# hpmon_pi_baseboard.net
KiCad netlist of a schematic drawn in EAGLE
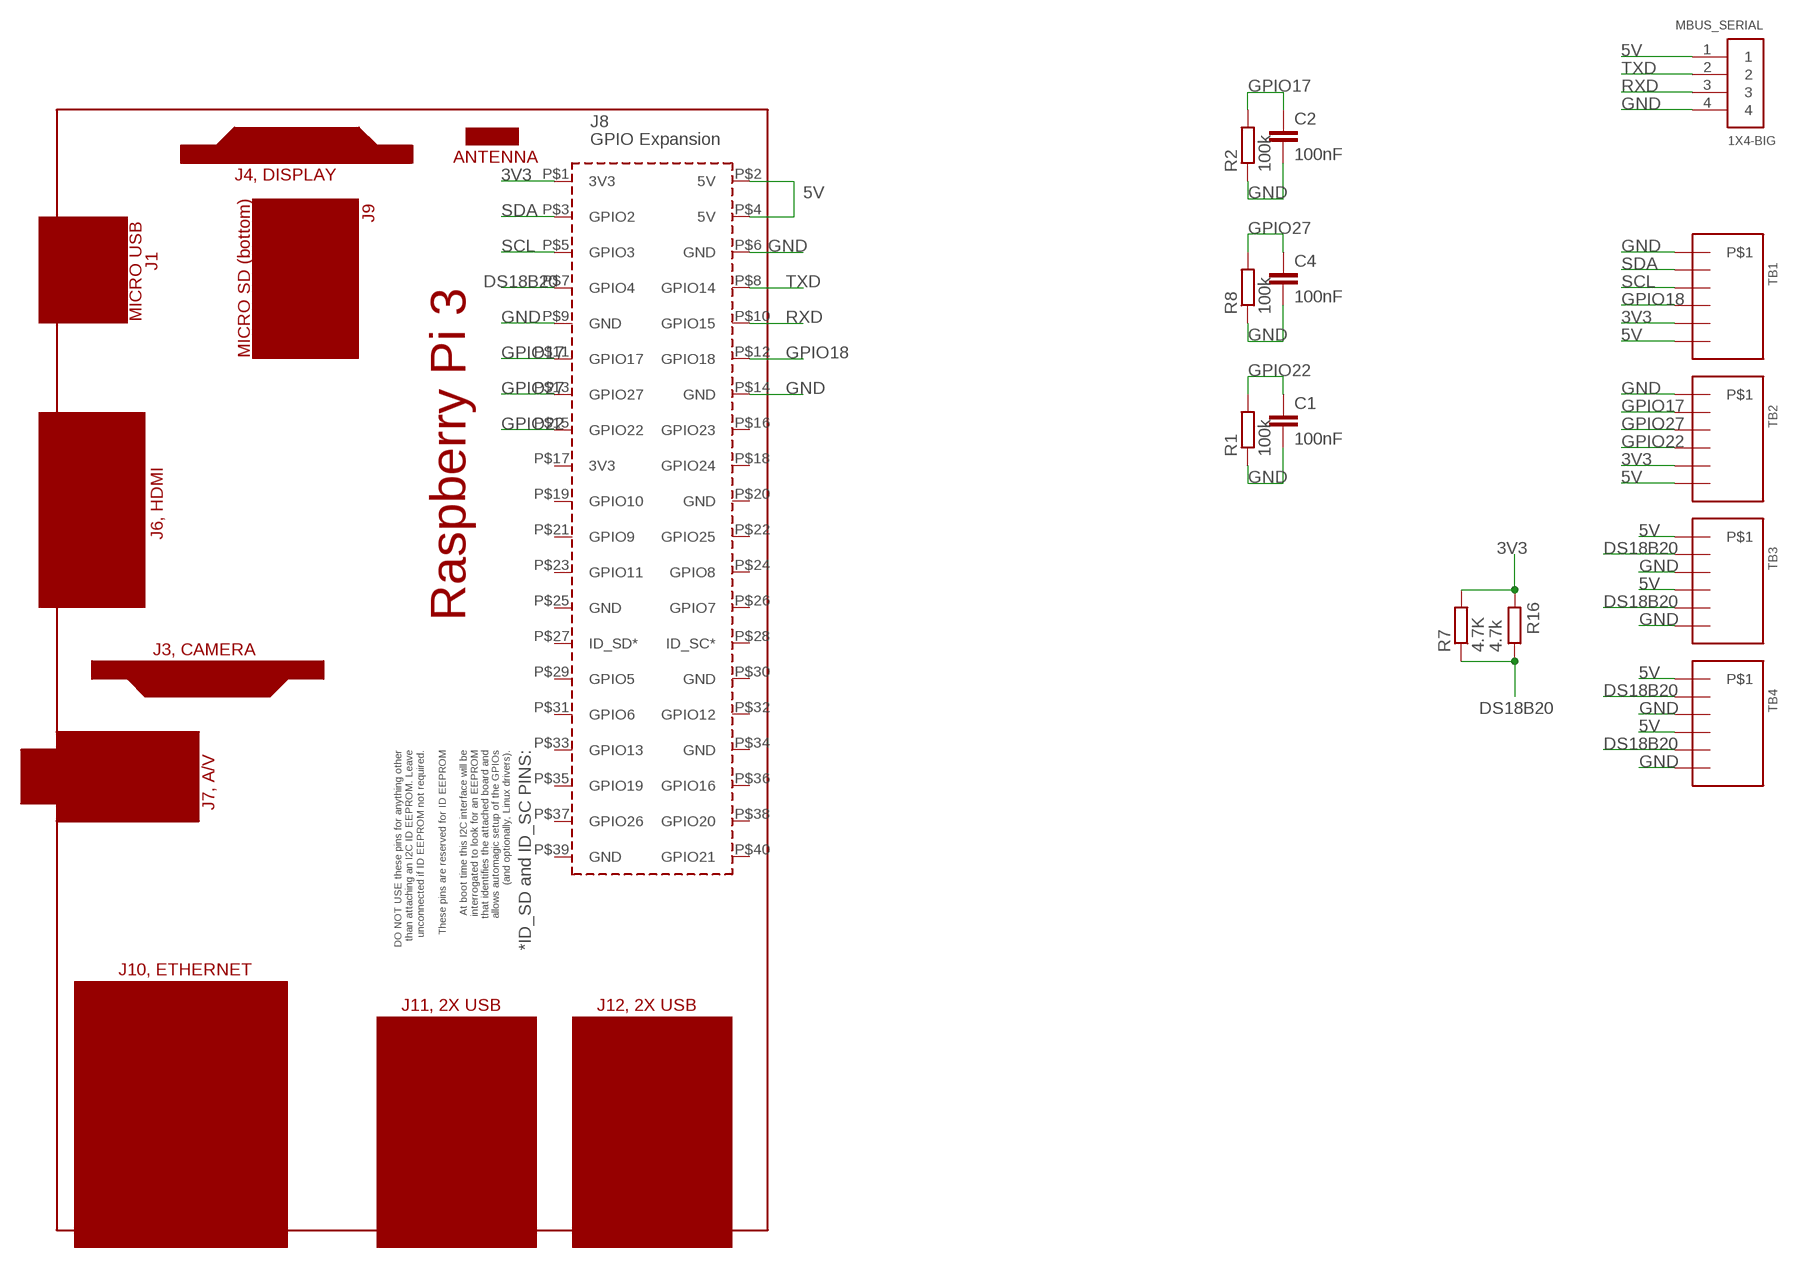
[diagram p0: schematic, sheet 1]

(export (version "E")
  (design (tool "Eeschema 10.0.6"))
  (components
    (comp (ref "C1")
      (value "100nF")
      (footprint "eagle-import:C025-024X044")
      (libsource (lib "eagle-import") (part "C-EU025-024X044"))
    )
    (comp (ref "C2")
      (value "100nF")
      (footprint "eagle-import:C025-024X044")
      (libsource (lib "eagle-import") (part "C-EU025-024X044"))
    )
    (comp (ref "C4")
      (value "100nF")
      (footprint "eagle-import:C025-024X044")
      (libsource (lib "eagle-import") (part "C-EU025-024X044"))
    )
    (comp (ref "MBUS_SERIAL")
      (value "1X4-BIG")
      (footprint "eagle-import:1X04-BIG")
      (libsource (lib "eagle-import") (part "1X4-BIG"))
    )
    (comp (ref "PCB1")
      (value "RPI3RPI3")
      (footprint "eagle-import:RPI3")
      (libsource (lib "eagle-import") (part "RPI3RPI3"))
    )
    (comp (ref "R1")
      (value "100k")
      (footprint "eagle-import:0207_2V")
      (libsource (lib "eagle-import") (part "R-EU_0207/2V"))
    )
    (comp (ref "R2")
      (value "100k")
      (footprint "eagle-import:0207_2V")
      (libsource (lib "eagle-import") (part "R-EU_0207/2V"))
    )
    (comp (ref "R7")
      (value "4.7K")
      (footprint "eagle-import:0204_7")
      (libsource (lib "eagle-import") (part "resistor_R-EU_0204/7"))
    )
    (comp (ref "R8")
      (value "100k")
      (footprint "eagle-import:0207_2V")
      (libsource (lib "eagle-import") (part "R-EU_0207/2V"))
    )
    (comp (ref "R16")
      (value "4.7k")
      (footprint "eagle-import:R0603")
      (libsource (lib "eagle-import") (part "R-EU_R0603"))
    )
    (comp (ref "TB1")
      (value "3.5MM_TB_X6")
      (footprint "eagle-import:3.5MM_X6")
      (libsource (lib "eagle-import") (part "3.5MM_TB_X6"))
    )
    (comp (ref "TB2")
      (value "3.5MM_TB_X6")
      (footprint "eagle-import:3.5MM_X6")
      (libsource (lib "eagle-import") (part "3.5MM_TB_X6"))
    )
    (comp (ref "TB3")
      (value "3.5MM_TB_X6")
      (footprint "eagle-import:3.5MM_X6")
      (libsource (lib "eagle-import") (part "3.5MM_TB_X6"))
    )
    (comp (ref "TB4")
      (value "3.5MM_TB_X6")
      (footprint "eagle-import:3.5MM_X6")
      (libsource (lib "eagle-import") (part "3.5MM_TB_X6"))
    )
  )
  (nets
    (net (code "1") (name "/3V3") (class "Default")
      (node (ref "PCB1") (pin "P$1") (pinfunction "3V3_P$1") (pintype "bidirectional"))
      (node (ref "R16") (pin "2") (pinfunction "2_2") (pintype "passive"))
      (node (ref "R7") (pin "2") (pinfunction "2_2") (pintype "passive"))
      (node (ref "TB1") (pin "P$5") (pinfunction "P$5_P$5") (pintype "bidirectional"))
      (node (ref "TB2") (pin "P$5") (pinfunction "P$5_P$5") (pintype "bidirectional"))
    )
    (net (code "2") (name "/5V") (class "Default")
      (node (ref "MBUS_SERIAL") (pin "1") (pinfunction "1_1") (pintype "bidirectional"))
      (node (ref "PCB1") (pin "P$2") (pinfunction "5V_P$2") (pintype "bidirectional"))
      (node (ref "PCB1") (pin "P$4") (pinfunction "5V_P$4") (pintype "bidirectional"))
      (node (ref "TB1") (pin "P$6") (pinfunction "P$6_P$6") (pintype "bidirectional"))
      (node (ref "TB2") (pin "P$6") (pinfunction "P$6_P$6") (pintype "bidirectional"))
      (node (ref "TB3") (pin "P$1") (pinfunction "P$1_P$1") (pintype "bidirectional"))
      (node (ref "TB3") (pin "P$4") (pinfunction "P$4_P$4") (pintype "bidirectional"))
      (node (ref "TB4") (pin "P$1") (pinfunction "P$1_P$1") (pintype "bidirectional"))
      (node (ref "TB4") (pin "P$4") (pinfunction "P$4_P$4") (pintype "bidirectional"))
    )
    (net (code "3") (name "/DS18B20") (class "Default")
      (node (ref "PCB1") (pin "P$7") (pinfunction "GPIO4_P$7") (pintype "bidirectional"))
      (node (ref "R16") (pin "1") (pinfunction "1_1") (pintype "passive"))
      (node (ref "R7") (pin "1") (pinfunction "1_1") (pintype "passive"))
      (node (ref "TB3") (pin "P$2") (pinfunction "P$2_P$2") (pintype "bidirectional"))
      (node (ref "TB3") (pin "P$5") (pinfunction "P$5_P$5") (pintype "bidirectional"))
      (node (ref "TB4") (pin "P$2") (pinfunction "P$2_P$2") (pintype "bidirectional"))
      (node (ref "TB4") (pin "P$5") (pinfunction "P$5_P$5") (pintype "bidirectional"))
    )
    (net (code "4") (name "/GND") (class "Default")
      (node (ref "C1") (pin "2") (pinfunction "2_2") (pintype "passive"))
      (node (ref "C2") (pin "2") (pinfunction "2_2") (pintype "passive"))
      (node (ref "C4") (pin "2") (pinfunction "2_2") (pintype "passive"))
      (node (ref "MBUS_SERIAL") (pin "4") (pinfunction "4_4") (pintype "bidirectional"))
      (node (ref "PCB1") (pin "P$14") (pinfunction "GND_P$14") (pintype "bidirectional"))
      (node (ref "PCB1") (pin "P$6") (pinfunction "GND_P$6") (pintype "bidirectional"))
      (node (ref "PCB1") (pin "P$9") (pinfunction "GND_P$9") (pintype "bidirectional"))
      (node (ref "R1") (pin "1") (pinfunction "1_1") (pintype "passive"))
      (node (ref "R2") (pin "1") (pinfunction "1_1") (pintype "passive"))
      (node (ref "R8") (pin "1") (pinfunction "1_1") (pintype "passive"))
      (node (ref "TB1") (pin "P$1") (pinfunction "P$1_P$1") (pintype "bidirectional"))
      (node (ref "TB2") (pin "P$1") (pinfunction "P$1_P$1") (pintype "bidirectional"))
      (node (ref "TB3") (pin "P$3") (pinfunction "P$3_P$3") (pintype "bidirectional"))
      (node (ref "TB3") (pin "P$6") (pinfunction "P$6_P$6") (pintype "bidirectional"))
      (node (ref "TB4") (pin "P$3") (pinfunction "P$3_P$3") (pintype "bidirectional"))
      (node (ref "TB4") (pin "P$6") (pinfunction "P$6_P$6") (pintype "bidirectional"))
    )
    (net (code "5") (name "/GPIO17") (class "Default")
      (node (ref "C2") (pin "1") (pinfunction "1_1") (pintype "passive"))
      (node (ref "PCB1") (pin "P$11") (pinfunction "GPIO17_P$11") (pintype "bidirectional"))
      (node (ref "R2") (pin "2") (pinfunction "2_2") (pintype "passive"))
      (node (ref "TB2") (pin "P$2") (pinfunction "P$2_P$2") (pintype "bidirectional"))
    )
    (net (code "6") (name "/GPIO18") (class "Default")
      (node (ref "PCB1") (pin "P$12") (pinfunction "GPIO18_P$12") (pintype "bidirectional"))
      (node (ref "TB1") (pin "P$4") (pinfunction "P$4_P$4") (pintype "bidirectional"))
    )
    (net (code "7") (name "/GPIO22") (class "Default")
      (node (ref "C1") (pin "1") (pinfunction "1_1") (pintype "passive"))
      (node (ref "PCB1") (pin "P$15") (pinfunction "GPIO22_P$15") (pintype "bidirectional"))
      (node (ref "R1") (pin "2") (pinfunction "2_2") (pintype "passive"))
      (node (ref "TB2") (pin "P$4") (pinfunction "P$4_P$4") (pintype "bidirectional"))
    )
    (net (code "8") (name "/GPIO27") (class "Default")
      (node (ref "C4") (pin "1") (pinfunction "1_1") (pintype "passive"))
      (node (ref "PCB1") (pin "P$13") (pinfunction "GPIO27_P$13") (pintype "bidirectional"))
      (node (ref "R8") (pin "2") (pinfunction "2_2") (pintype "passive"))
      (node (ref "TB2") (pin "P$3") (pinfunction "P$3_P$3") (pintype "bidirectional"))
    )
    (net (code "9") (name "/RXD") (class "Default")
      (node (ref "MBUS_SERIAL") (pin "3") (pinfunction "3_3") (pintype "bidirectional"))
      (node (ref "PCB1") (pin "P$10") (pinfunction "GPIO15_P$10") (pintype "bidirectional"))
    )
    (net (code "10") (name "/SCL") (class "Default")
      (node (ref "PCB1") (pin "P$5") (pinfunction "GPIO3_P$5") (pintype "bidirectional"))
      (node (ref "TB1") (pin "P$3") (pinfunction "P$3_P$3") (pintype "bidirectional"))
    )
    (net (code "11") (name "/SDA") (class "Default")
      (node (ref "PCB1") (pin "P$3") (pinfunction "GPIO2_P$3") (pintype "bidirectional"))
      (node (ref "TB1") (pin "P$2") (pinfunction "P$2_P$2") (pintype "bidirectional"))
    )
    (net (code "12") (name "/TXD") (class "Default")
      (node (ref "MBUS_SERIAL") (pin "2") (pinfunction "2_2") (pintype "bidirectional"))
      (node (ref "PCB1") (pin "P$8") (pinfunction "GPIO14_P$8") (pintype "bidirectional"))
    )
    (net (code "13") (name "unconnected-(PCB1-3V3-PadP$17)") (class "Default")
      (node (ref "PCB1") (pin "P$17") (pinfunction "3V3_P$17") (pintype "bidirectional"))
    )
    (net (code "14") (name "unconnected-(PCB1-GND-PadP$20)") (class "Default")
      (node (ref "PCB1") (pin "P$20") (pinfunction "GND_P$20") (pintype "bidirectional"))
    )
    (net (code "15") (name "unconnected-(PCB1-GND-PadP$25)") (class "Default")
      (node (ref "PCB1") (pin "P$25") (pinfunction "GND_P$25") (pintype "bidirectional"))
    )
    (net (code "16") (name "unconnected-(PCB1-GND-PadP$30)") (class "Default")
      (node (ref "PCB1") (pin "P$30") (pinfunction "GND_P$30") (pintype "bidirectional"))
    )
    (net (code "17") (name "unconnected-(PCB1-GND-PadP$34)") (class "Default")
      (node (ref "PCB1") (pin "P$34") (pinfunction "GND_P$34") (pintype "bidirectional"))
    )
    (net (code "18") (name "unconnected-(PCB1-GND-PadP$39)") (class "Default")
      (node (ref "PCB1") (pin "P$39") (pinfunction "GND_P$39") (pintype "bidirectional"))
    )
    (net (code "19") (name "unconnected-(PCB1-GPIO5-PadP$29)") (class "Default")
      (node (ref "PCB1") (pin "P$29") (pinfunction "GPIO5_P$29") (pintype "bidirectional"))
    )
    (net (code "20") (name "unconnected-(PCB1-GPIO6-PadP$31)") (class "Default")
      (node (ref "PCB1") (pin "P$31") (pinfunction "GPIO6_P$31") (pintype "bidirectional"))
    )
    (net (code "21") (name "unconnected-(PCB1-GPIO7-PadP$26)") (class "Default")
      (node (ref "PCB1") (pin "P$26") (pinfunction "GPIO7_P$26") (pintype "bidirectional"))
    )
    (net (code "22") (name "unconnected-(PCB1-GPIO8-PadP$24)") (class "Default")
      (node (ref "PCB1") (pin "P$24") (pinfunction "GPIO8_P$24") (pintype "bidirectional"))
    )
    (net (code "23") (name "unconnected-(PCB1-GPIO9-PadP$21)") (class "Default")
      (node (ref "PCB1") (pin "P$21") (pinfunction "GPIO9_P$21") (pintype "bidirectional"))
    )
    (net (code "24") (name "unconnected-(PCB1-GPIO10-PadP$19)") (class "Default")
      (node (ref "PCB1") (pin "P$19") (pinfunction "GPIO10_P$19") (pintype "bidirectional"))
    )
    (net (code "25") (name "unconnected-(PCB1-GPIO11-PadP$23)") (class "Default")
      (node (ref "PCB1") (pin "P$23") (pinfunction "GPIO11_P$23") (pintype "bidirectional"))
    )
    (net (code "26") (name "unconnected-(PCB1-GPIO12-PadP$32)") (class "Default")
      (node (ref "PCB1") (pin "P$32") (pinfunction "GPIO12_P$32") (pintype "bidirectional"))
    )
    (net (code "27") (name "unconnected-(PCB1-GPIO13-PadP$33)") (class "Default")
      (node (ref "PCB1") (pin "P$33") (pinfunction "GPIO13_P$33") (pintype "bidirectional"))
    )
    (net (code "28") (name "unconnected-(PCB1-GPIO16-PadP$36)") (class "Default")
      (node (ref "PCB1") (pin "P$36") (pinfunction "GPIO16_P$36") (pintype "bidirectional"))
    )
    (net (code "29") (name "unconnected-(PCB1-GPIO19-PadP$35)") (class "Default")
      (node (ref "PCB1") (pin "P$35") (pinfunction "GPIO19_P$35") (pintype "bidirectional"))
    )
    (net (code "30") (name "unconnected-(PCB1-GPIO20-PadP$38)") (class "Default")
      (node (ref "PCB1") (pin "P$38") (pinfunction "GPIO20_P$38") (pintype "bidirectional"))
    )
    (net (code "31") (name "unconnected-(PCB1-GPIO21-PadP$40)") (class "Default")
      (node (ref "PCB1") (pin "P$40") (pinfunction "GPIO21_P$40") (pintype "bidirectional"))
    )
    (net (code "32") (name "unconnected-(PCB1-GPIO23-PadP$16)") (class "Default")
      (node (ref "PCB1") (pin "P$16") (pinfunction "GPIO23_P$16") (pintype "bidirectional"))
    )
    (net (code "33") (name "unconnected-(PCB1-GPIO24-PadP$18)") (class "Default")
      (node (ref "PCB1") (pin "P$18") (pinfunction "GPIO24_P$18") (pintype "bidirectional"))
    )
    (net (code "34") (name "unconnected-(PCB1-GPIO25-PadP$22)") (class "Default")
      (node (ref "PCB1") (pin "P$22") (pinfunction "GPIO25_P$22") (pintype "bidirectional"))
    )
    (net (code "35") (name "unconnected-(PCB1-GPIO26-PadP$37)") (class "Default")
      (node (ref "PCB1") (pin "P$37") (pinfunction "GPIO26_P$37") (pintype "bidirectional"))
    )
    (net (code "36") (name "unconnected-(PCB1-ID_SC*-PadP$28)") (class "Default")
      (node (ref "PCB1") (pin "P$28") (pinfunction "ID_SC*_P$28") (pintype "bidirectional"))
    )
    (net (code "37") (name "unconnected-(PCB1-ID_SD*-PadP$27)") (class "Default")
      (node (ref "PCB1") (pin "P$27") (pinfunction "ID_SD*_P$27") (pintype "bidirectional"))
    )
  )
)
